# AVRI2CIO_V0_3_LEVEL1.net
KiCad netlist of a schematic drawn in EAGLE
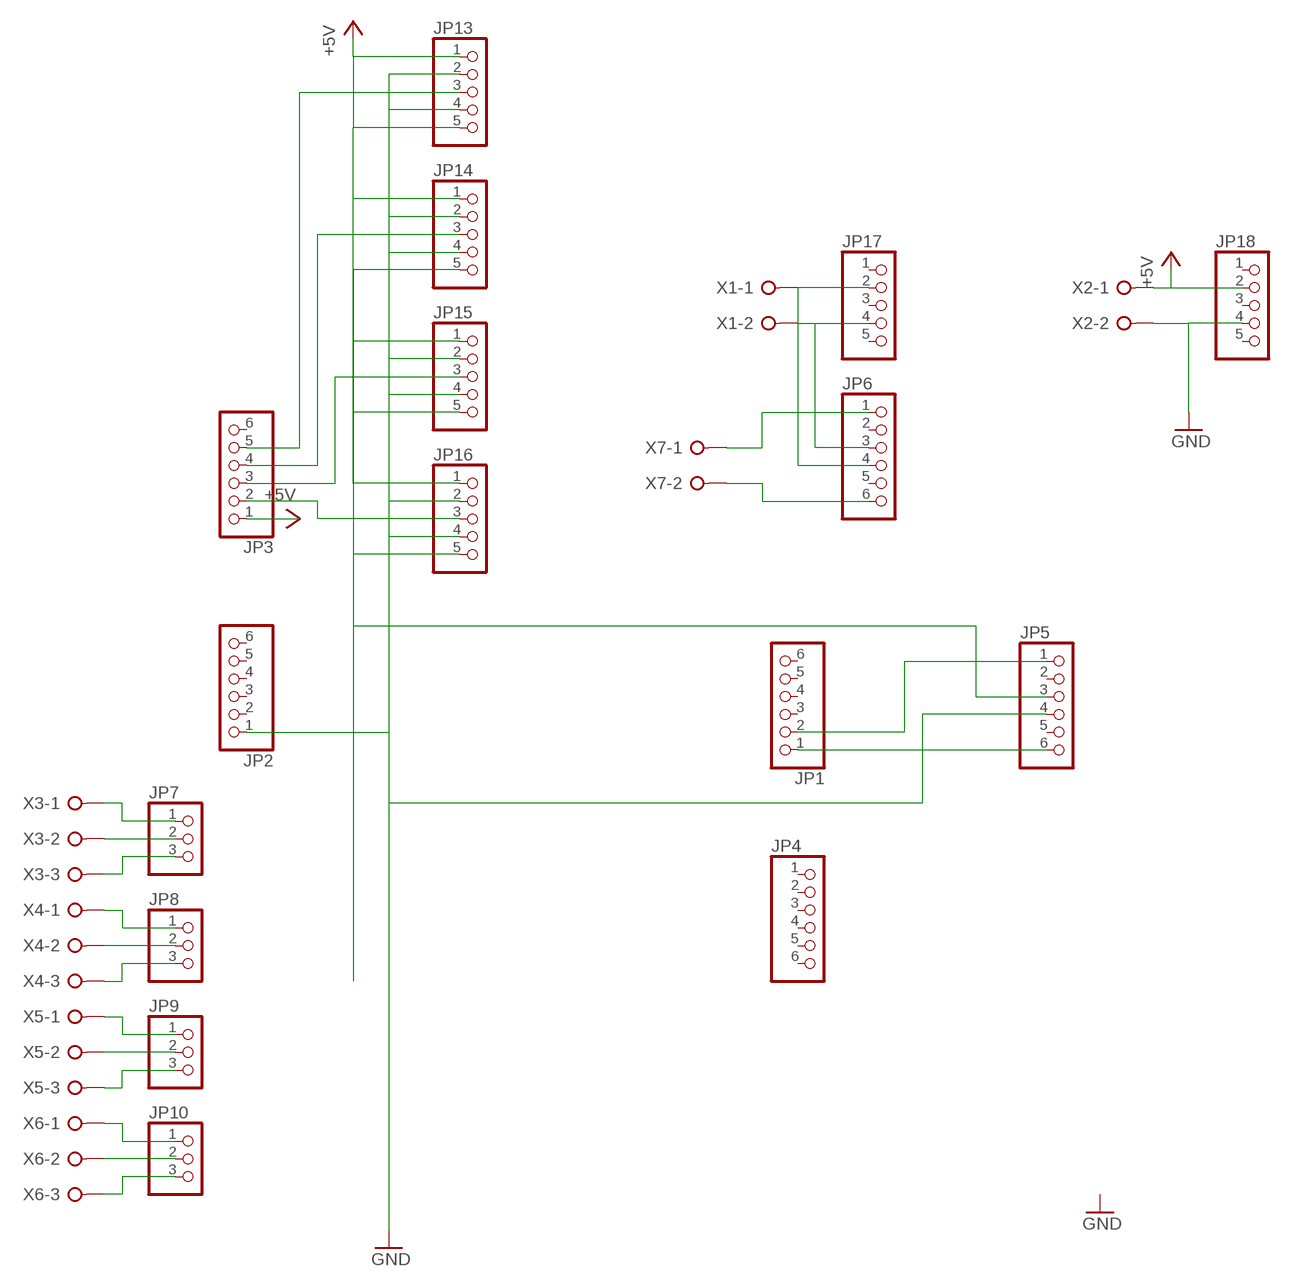
[diagram p0: schematic, sheet 1]

(export (version "E")
  (design (tool "Eeschema 10.0.6"))
  (components
    (comp (ref "JP1")
      (value "PINHD-1X6")
      (footprint "eagle-import:1X06")
      (libsource (lib "eagle-import") (part "PINHD-1X6"))
    )
    (comp (ref "JP2")
      (value "PINHD-1X6")
      (footprint "eagle-import:1X06")
      (libsource (lib "eagle-import") (part "PINHD-1X6"))
    )
    (comp (ref "JP3")
      (value "PINHD-1X6")
      (footprint "eagle-import:1X06")
      (libsource (lib "eagle-import") (part "PINHD-1X6"))
    )
    (comp (ref "JP4")
      (value "PINHD-1X6")
      (footprint "eagle-import:1X06")
      (libsource (lib "eagle-import") (part "PINHD-1X6"))
    )
    (comp (ref "JP5")
      (value "PINHD-1X6")
      (footprint "eagle-import:1X06")
      (libsource (lib "eagle-import") (part "PINHD-1X6"))
    )
    (comp (ref "JP6")
      (value "PINHD-1X6")
      (footprint "eagle-import:1X06")
      (libsource (lib "eagle-import") (part "PINHD-1X6"))
    )
    (comp (ref "JP7")
      (value "PINHD-1X3")
      (footprint "eagle-import:1X03")
      (libsource (lib "eagle-import") (part "PINHD-1X3"))
    )
    (comp (ref "JP8")
      (value "PINHD-1X3")
      (footprint "eagle-import:1X03")
      (libsource (lib "eagle-import") (part "PINHD-1X3"))
    )
    (comp (ref "JP9")
      (value "PINHD-1X3")
      (footprint "eagle-import:1X03")
      (libsource (lib "eagle-import") (part "PINHD-1X3"))
    )
    (comp (ref "JP10")
      (value "PINHD-1X3")
      (footprint "eagle-import:1X03")
      (libsource (lib "eagle-import") (part "PINHD-1X3"))
    )
    (comp (ref "JP13")
      (value "PINHD-1X5")
      (footprint "eagle-import:1X05")
      (libsource (lib "eagle-import") (part "PINHD-1X5"))
    )
    (comp (ref "JP14")
      (value "PINHD-1X5")
      (footprint "eagle-import:1X05")
      (libsource (lib "eagle-import") (part "PINHD-1X5"))
    )
    (comp (ref "JP15")
      (value "PINHD-1X5")
      (footprint "eagle-import:1X05")
      (libsource (lib "eagle-import") (part "PINHD-1X5"))
    )
    (comp (ref "JP16")
      (value "PINHD-1X5")
      (footprint "eagle-import:1X05")
      (libsource (lib "eagle-import") (part "PINHD-1X5"))
    )
    (comp (ref "JP17")
      (value "PINHD-1X5")
      (footprint "eagle-import:1X05")
      (libsource (lib "eagle-import") (part "PINHD-1X5"))
    )
    (comp (ref "JP18")
      (value "PINHD-1X5")
      (footprint "eagle-import:1X05")
      (libsource (lib "eagle-import") (part "PINHD-1X5"))
    )
    (comp (ref "X1")
      (value "W237-02P")
      (footprint "eagle-import:W237-132")
      (libsource (lib "eagle-import") (part "W237-02P"))
    )
    (comp (ref "X2")
      (value "W237-02P")
      (footprint "eagle-import:W237-132")
      (libsource (lib "eagle-import") (part "W237-02P"))
    )
    (comp (ref "X3")
      (value "W237-3E")
      (footprint "eagle-import:W237-3E")
      (libsource (lib "eagle-import") (part "W237-3E"))
    )
    (comp (ref "X4")
      (value "W237-3E")
      (footprint "eagle-import:W237-3E")
      (libsource (lib "eagle-import") (part "W237-3E"))
    )
    (comp (ref "X5")
      (value "W237-3E")
      (footprint "eagle-import:W237-3E")
      (libsource (lib "eagle-import") (part "W237-3E"))
    )
    (comp (ref "X6")
      (value "W237-3E")
      (footprint "eagle-import:W237-3E")
      (libsource (lib "eagle-import") (part "W237-3E"))
    )
    (comp (ref "X7")
      (value "W237-02P")
      (footprint "eagle-import:W237-132")
      (libsource (lib "eagle-import") (part "W237-02P"))
    )
  )
  (nets
    (net (code "1") (name "+5V") (class "Default")
      (node (ref "JP13") (pin "1") (pinfunction "1_1") (pintype "passive"))
      (node (ref "JP13") (pin "5") (pinfunction "5_5") (pintype "passive"))
      (node (ref "JP14") (pin "5") (pinfunction "5_5") (pintype "passive"))
      (node (ref "JP15") (pin "1") (pinfunction "1_1") (pintype "passive"))
      (node (ref "JP15") (pin "5") (pinfunction "5_5") (pintype "passive"))
      (node (ref "JP16") (pin "1") (pinfunction "1_1") (pintype "passive"))
      (node (ref "JP16") (pin "5") (pinfunction "5_5") (pintype "passive"))
      (node (ref "JP18") (pin "2") (pinfunction "2_2") (pintype "passive"))
      (node (ref "JP3") (pin "1") (pinfunction "1_1") (pintype "passive"))
      (node (ref "JP5") (pin "3") (pinfunction "3_3") (pintype "passive"))
      (node (ref "X2") (pin "1") (pinfunction "KL_1") (pintype "passive"))
    )
    (net (code "2") (name "GND") (class "Default")
      (node (ref "JP13") (pin "2") (pinfunction "2_2") (pintype "passive"))
      (node (ref "JP13") (pin "4") (pinfunction "4_4") (pintype "passive"))
      (node (ref "JP14") (pin "2") (pinfunction "2_2") (pintype "passive"))
      (node (ref "JP14") (pin "4") (pinfunction "4_4") (pintype "passive"))
      (node (ref "JP15") (pin "2") (pinfunction "2_2") (pintype "passive"))
      (node (ref "JP15") (pin "4") (pinfunction "4_4") (pintype "passive"))
      (node (ref "JP16") (pin "2") (pinfunction "2_2") (pintype "passive"))
      (node (ref "JP16") (pin "4") (pinfunction "4_4") (pintype "passive"))
      (node (ref "JP18") (pin "4") (pinfunction "4_4") (pintype "passive"))
      (node (ref "JP2") (pin "1") (pinfunction "1_1") (pintype "passive"))
      (node (ref "JP5") (pin "4") (pinfunction "4_4") (pintype "passive"))
      (node (ref "X2") (pin "2") (pinfunction "KL_2") (pintype "passive"))
    )
    (net (code "3") (name "Net-(JP1-Pad1)") (class "Default")
      (node (ref "JP1") (pin "1") (pinfunction "1_1") (pintype "passive"))
      (node (ref "JP5") (pin "6") (pinfunction "6_6") (pintype "passive"))
    )
    (net (code "4") (name "Net-(JP1-Pad2)") (class "Default")
      (node (ref "JP1") (pin "2") (pinfunction "2_2") (pintype "passive"))
      (node (ref "JP5") (pin "1") (pinfunction "1_1") (pintype "passive"))
    )
    (net (code "5") (name "Net-(JP13-Pad3)") (class "Default")
      (node (ref "JP13") (pin "3") (pinfunction "3_3") (pintype "passive"))
      (node (ref "JP3") (pin "5") (pinfunction "5_5") (pintype "passive"))
    )
    (net (code "6") (name "Net-(JP14-Pad3)") (class "Default")
      (node (ref "JP14") (pin "3") (pinfunction "3_3") (pintype "passive"))
      (node (ref "JP3") (pin "4") (pinfunction "4_4") (pintype "passive"))
    )
    (net (code "7") (name "Net-(JP15-Pad3)") (class "Default")
      (node (ref "JP15") (pin "3") (pinfunction "3_3") (pintype "passive"))
      (node (ref "JP3") (pin "3") (pinfunction "3_3") (pintype "passive"))
    )
    (net (code "8") (name "Net-(JP16-Pad3)") (class "Default")
      (node (ref "JP16") (pin "3") (pinfunction "3_3") (pintype "passive"))
      (node (ref "JP3") (pin "2") (pinfunction "2_2") (pintype "passive"))
    )
    (net (code "9") (name "Net-(X1A-KL)") (class "Default")
      (node (ref "JP17") (pin "2") (pinfunction "2_2") (pintype "passive"))
      (node (ref "JP6") (pin "4") (pinfunction "4_4") (pintype "passive"))
      (node (ref "X1") (pin "1") (pinfunction "KL_1") (pintype "passive"))
    )
    (net (code "10") (name "Net-(X1B-KL)") (class "Default")
      (node (ref "JP17") (pin "4") (pinfunction "4_4") (pintype "passive"))
      (node (ref "JP6") (pin "3") (pinfunction "3_3") (pintype "passive"))
      (node (ref "X1") (pin "2") (pinfunction "KL_2") (pintype "passive"))
    )
    (net (code "11") (name "Net-(X3A-KL)") (class "Default")
      (node (ref "JP7") (pin "1") (pinfunction "1_1") (pintype "passive"))
      (node (ref "X3") (pin "1") (pinfunction "KL_1") (pintype "passive"))
    )
    (net (code "12") (name "Net-(X3B-KL)") (class "Default")
      (node (ref "JP7") (pin "2") (pinfunction "2_2") (pintype "passive"))
      (node (ref "X3") (pin "2") (pinfunction "KL_2") (pintype "passive"))
    )
    (net (code "13") (name "Net-(X3C-KL)") (class "Default")
      (node (ref "JP7") (pin "3") (pinfunction "3_3") (pintype "passive"))
      (node (ref "X3") (pin "3") (pinfunction "KL_3") (pintype "passive"))
    )
    (net (code "14") (name "Net-(X4A-KL)") (class "Default")
      (node (ref "JP8") (pin "1") (pinfunction "1_1") (pintype "passive"))
      (node (ref "X4") (pin "1") (pinfunction "KL_1") (pintype "passive"))
    )
    (net (code "15") (name "Net-(X4B-KL)") (class "Default")
      (node (ref "JP8") (pin "2") (pinfunction "2_2") (pintype "passive"))
      (node (ref "X4") (pin "2") (pinfunction "KL_2") (pintype "passive"))
    )
    (net (code "16") (name "Net-(X4C-KL)") (class "Default")
      (node (ref "JP8") (pin "3") (pinfunction "3_3") (pintype "passive"))
      (node (ref "X4") (pin "3") (pinfunction "KL_3") (pintype "passive"))
    )
    (net (code "17") (name "Net-(X5A-KL)") (class "Default")
      (node (ref "JP9") (pin "1") (pinfunction "1_1") (pintype "passive"))
      (node (ref "X5") (pin "1") (pinfunction "KL_1") (pintype "passive"))
    )
    (net (code "18") (name "Net-(X5B-KL)") (class "Default")
      (node (ref "JP9") (pin "2") (pinfunction "2_2") (pintype "passive"))
      (node (ref "X5") (pin "2") (pinfunction "KL_2") (pintype "passive"))
    )
    (net (code "19") (name "Net-(X5C-KL)") (class "Default")
      (node (ref "JP9") (pin "3") (pinfunction "3_3") (pintype "passive"))
      (node (ref "X5") (pin "3") (pinfunction "KL_3") (pintype "passive"))
    )
    (net (code "20") (name "Net-(X6A-KL)") (class "Default")
      (node (ref "JP10") (pin "1") (pinfunction "1_1") (pintype "passive"))
      (node (ref "X6") (pin "1") (pinfunction "KL_1") (pintype "passive"))
    )
    (net (code "21") (name "Net-(X6B-KL)") (class "Default")
      (node (ref "JP10") (pin "2") (pinfunction "2_2") (pintype "passive"))
      (node (ref "X6") (pin "2") (pinfunction "KL_2") (pintype "passive"))
    )
    (net (code "22") (name "Net-(X6C-KL)") (class "Default")
      (node (ref "JP10") (pin "3") (pinfunction "3_3") (pintype "passive"))
      (node (ref "X6") (pin "3") (pinfunction "KL_3") (pintype "passive"))
    )
    (net (code "23") (name "Net-(X7A-KL)") (class "Default")
      (node (ref "JP6") (pin "1") (pinfunction "1_1") (pintype "passive"))
      (node (ref "X7") (pin "1") (pinfunction "KL_1") (pintype "passive"))
    )
    (net (code "24") (name "Net-(X7B-KL)") (class "Default")
      (node (ref "JP6") (pin "6") (pinfunction "6_6") (pintype "passive"))
      (node (ref "X7") (pin "2") (pinfunction "KL_2") (pintype "passive"))
    )
    (net (code "25") (name "unconnected-(JP1-Pad3)") (class "Default")
      (node (ref "JP1") (pin "3") (pinfunction "3_3") (pintype "passive"))
    )
    (net (code "26") (name "unconnected-(JP1-Pad4)") (class "Default")
      (node (ref "JP1") (pin "4") (pinfunction "4_4") (pintype "passive"))
    )
    (net (code "27") (name "unconnected-(JP1-Pad5)") (class "Default")
      (node (ref "JP1") (pin "5") (pinfunction "5_5") (pintype "passive"))
    )
    (net (code "28") (name "unconnected-(JP1-Pad6)") (class "Default")
      (node (ref "JP1") (pin "6") (pinfunction "6_6") (pintype "passive"))
    )
    (net (code "29") (name "unconnected-(JP2-Pad2)") (class "Default")
      (node (ref "JP2") (pin "2") (pinfunction "2_2") (pintype "passive"))
    )
    (net (code "30") (name "unconnected-(JP2-Pad3)") (class "Default")
      (node (ref "JP2") (pin "3") (pinfunction "3_3") (pintype "passive"))
    )
    (net (code "31") (name "unconnected-(JP2-Pad4)") (class "Default")
      (node (ref "JP2") (pin "4") (pinfunction "4_4") (pintype "passive"))
    )
    (net (code "32") (name "unconnected-(JP2-Pad5)") (class "Default")
      (node (ref "JP2") (pin "5") (pinfunction "5_5") (pintype "passive"))
    )
    (net (code "33") (name "unconnected-(JP2-Pad6)") (class "Default")
      (node (ref "JP2") (pin "6") (pinfunction "6_6") (pintype "passive"))
    )
    (net (code "34") (name "unconnected-(JP3-Pad6)") (class "Default")
      (node (ref "JP3") (pin "6") (pinfunction "6_6") (pintype "passive"))
    )
    (net (code "35") (name "unconnected-(JP4-Pad1)") (class "Default")
      (node (ref "JP4") (pin "1") (pinfunction "1_1") (pintype "passive"))
    )
    (net (code "36") (name "unconnected-(JP4-Pad2)") (class "Default")
      (node (ref "JP4") (pin "2") (pinfunction "2_2") (pintype "passive"))
    )
    (net (code "37") (name "unconnected-(JP4-Pad3)") (class "Default")
      (node (ref "JP4") (pin "3") (pinfunction "3_3") (pintype "passive"))
    )
    (net (code "38") (name "unconnected-(JP4-Pad4)") (class "Default")
      (node (ref "JP4") (pin "4") (pinfunction "4_4") (pintype "passive"))
    )
    (net (code "39") (name "unconnected-(JP4-Pad5)") (class "Default")
      (node (ref "JP4") (pin "5") (pinfunction "5_5") (pintype "passive"))
    )
    (net (code "40") (name "unconnected-(JP4-Pad6)") (class "Default")
      (node (ref "JP4") (pin "6") (pinfunction "6_6") (pintype "passive"))
    )
    (net (code "41") (name "unconnected-(JP5-Pad2)") (class "Default")
      (node (ref "JP5") (pin "2") (pinfunction "2_2") (pintype "passive"))
    )
    (net (code "42") (name "unconnected-(JP5-Pad5)") (class "Default")
      (node (ref "JP5") (pin "5") (pinfunction "5_5") (pintype "passive"))
    )
    (net (code "43") (name "unconnected-(JP6-Pad2)") (class "Default")
      (node (ref "JP6") (pin "2") (pinfunction "2_2") (pintype "passive"))
    )
    (net (code "44") (name "unconnected-(JP6-Pad5)") (class "Default")
      (node (ref "JP6") (pin "5") (pinfunction "5_5") (pintype "passive"))
    )
    (net (code "45") (name "unconnected-(JP14-Pad1)") (class "Default")
      (node (ref "JP14") (pin "1") (pinfunction "1_1") (pintype "passive"))
    )
    (net (code "46") (name "unconnected-(JP17-Pad1)") (class "Default")
      (node (ref "JP17") (pin "1") (pinfunction "1_1") (pintype "passive"))
    )
    (net (code "47") (name "unconnected-(JP17-Pad3)") (class "Default")
      (node (ref "JP17") (pin "3") (pinfunction "3_3") (pintype "passive"))
    )
    (net (code "48") (name "unconnected-(JP17-Pad5)") (class "Default")
      (node (ref "JP17") (pin "5") (pinfunction "5_5") (pintype "passive"))
    )
    (net (code "49") (name "unconnected-(JP18-Pad1)") (class "Default")
      (node (ref "JP18") (pin "1") (pinfunction "1_1") (pintype "passive"))
    )
    (net (code "50") (name "unconnected-(JP18-Pad3)") (class "Default")
      (node (ref "JP18") (pin "3") (pinfunction "3_3") (pintype "passive"))
    )
    (net (code "51") (name "unconnected-(JP18-Pad5)") (class "Default")
      (node (ref "JP18") (pin "5") (pinfunction "5_5") (pintype "passive"))
    )
  )
)
